# ZHSD-BOOT-STORAGE.net
KiCad netlist of a schematic drawn in Altium Designer
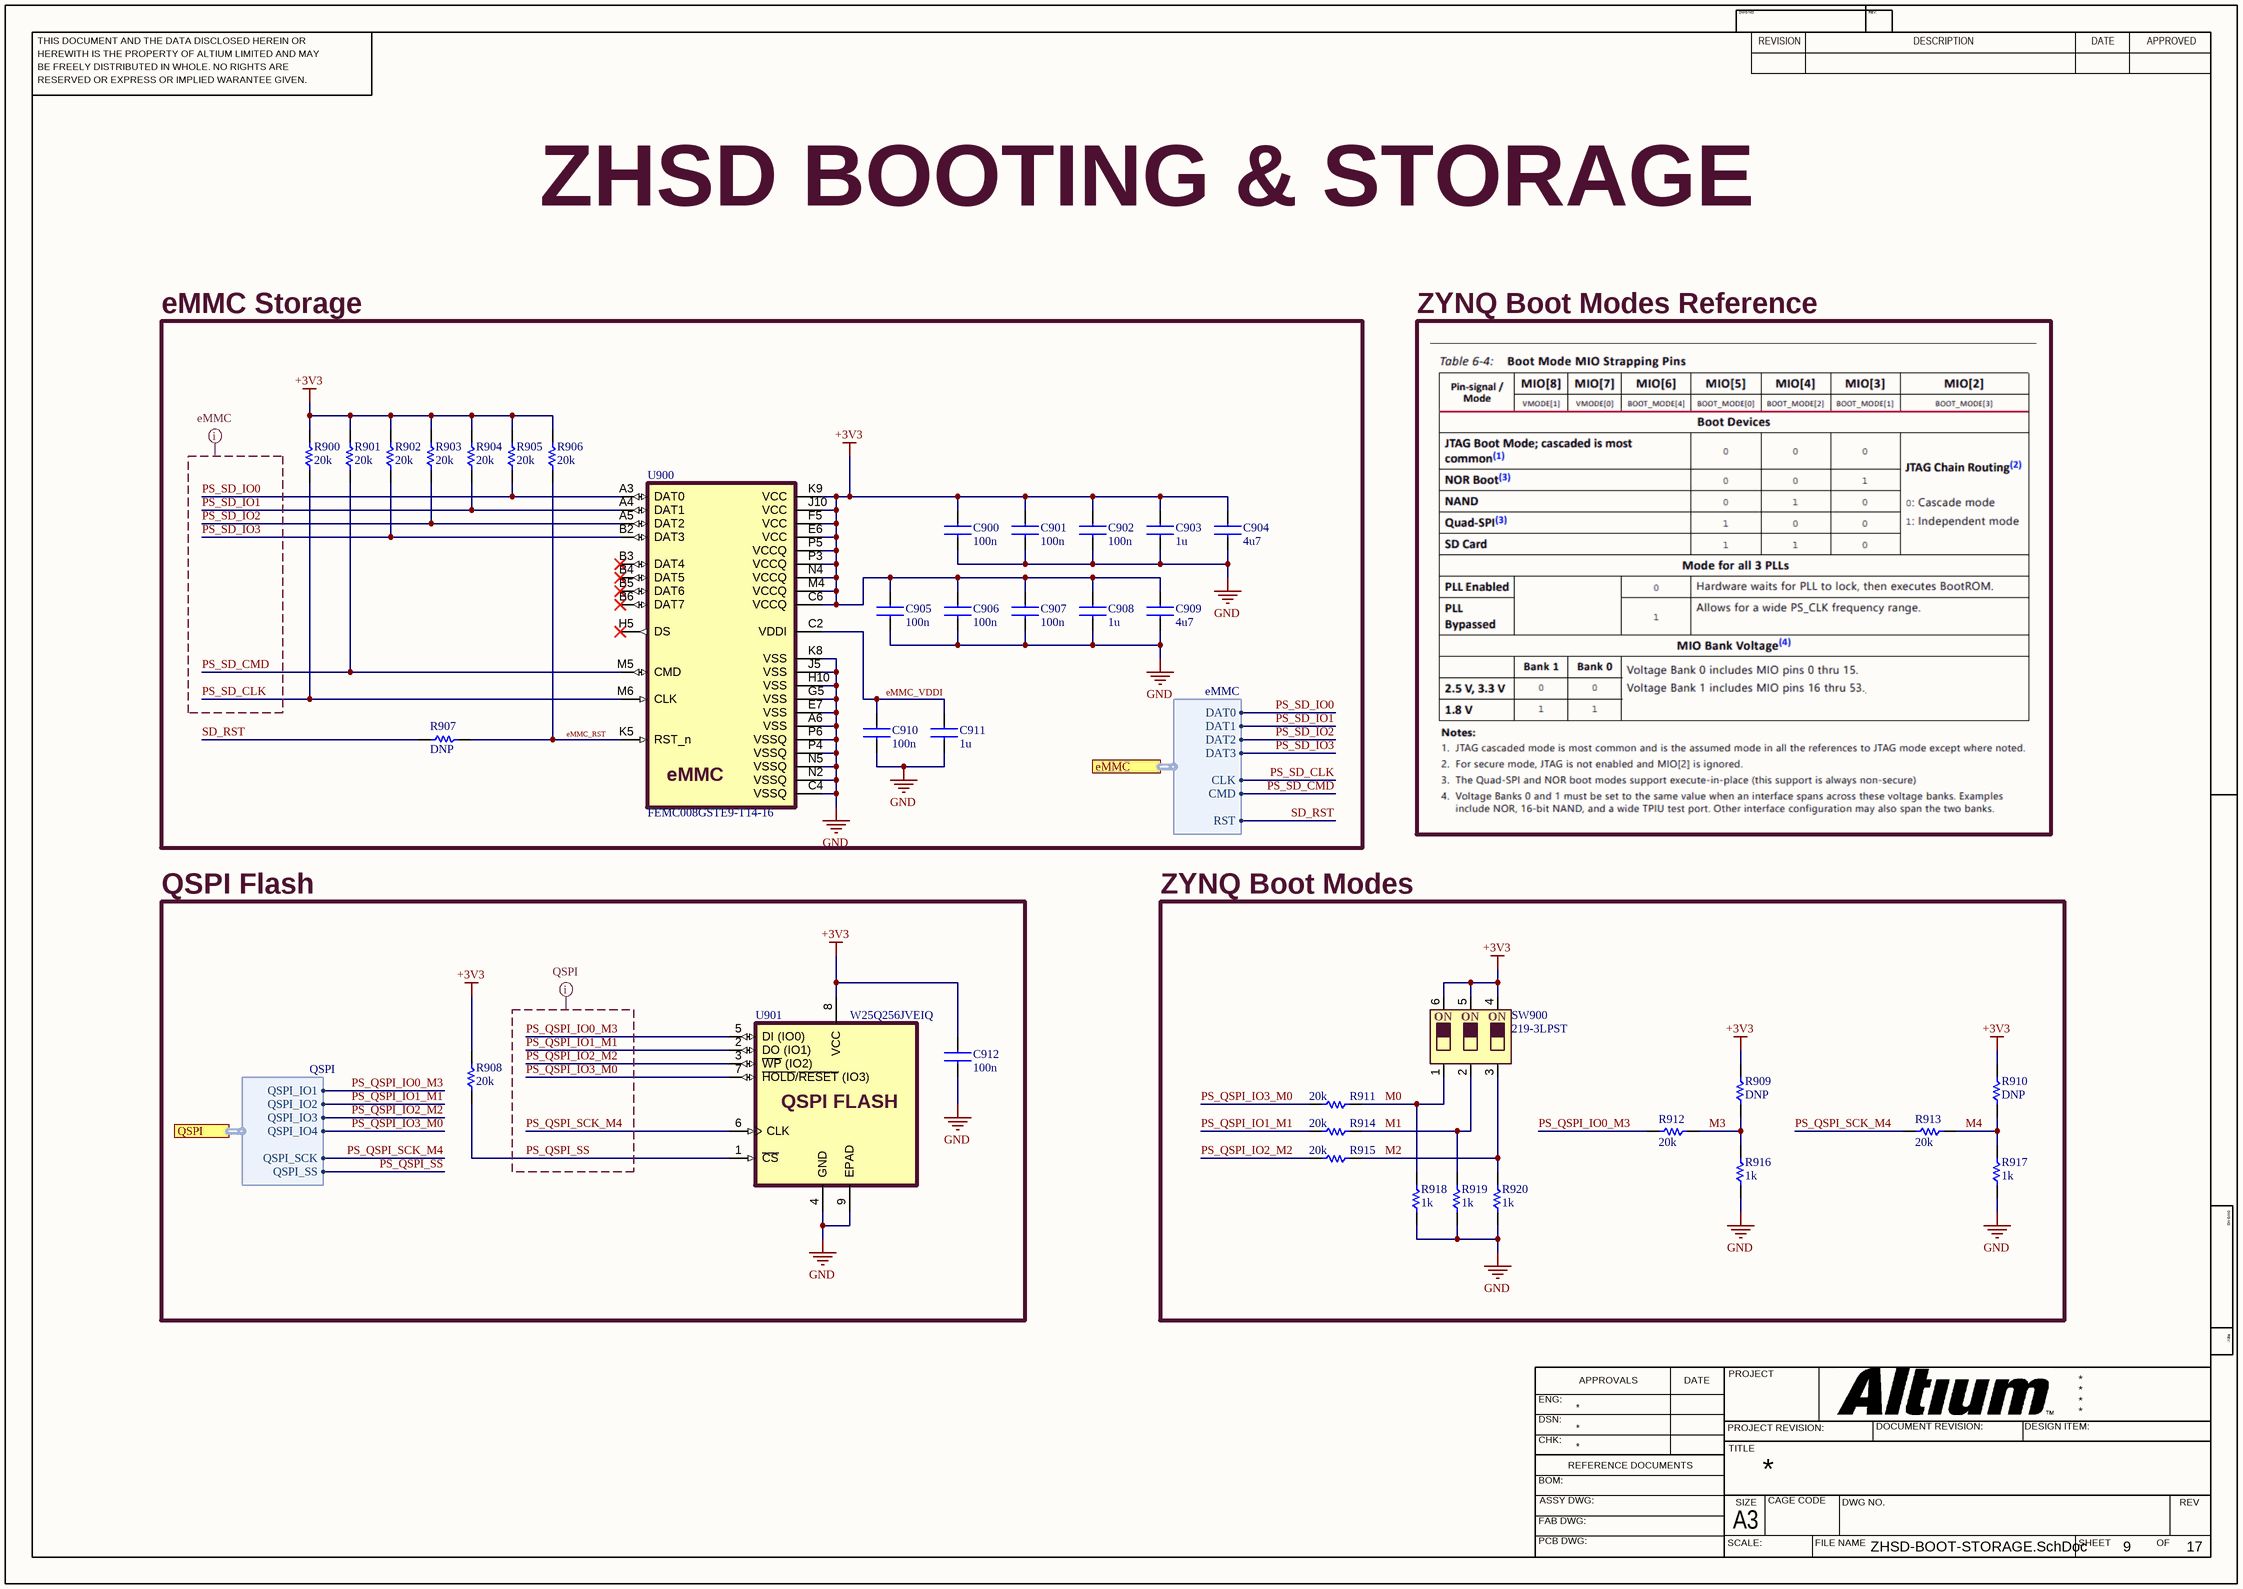
[diagram p0: ZHSD-BOOT-STORAGE.SchDoc]

(export (version "E")
  (design (tool "Eeschema 10.0.6"))
  (components
    (comp (ref "C900")
      (value "100n")
      (footprint "0603CAPC1608X09N")
      (description "CAP CER 0.1UF 16V X7R 0402 (1005) ±10%")
      (fields (field (name "MANUFACTURER") "Murata Electronics") (field (name "MPN") "GRM155R71C104KA88J"))
      (libsource (lib "UK_Library") (part "GRM155R71C104KA88J"))
    )
    (comp (ref "C901")
      (value "100n")
      (footprint "0603CAPC1608X09N")
      (description "CAP CER 0.1UF 16V X7R 0402 (1005) ±10%")
      (fields (field (name "MANUFACTURER") "Murata Electronics") (field (name "MPN") "GRM155R71C104KA88J"))
      (libsource (lib "UK_Library") (part "GRM155R71C104KA88J"))
    )
    (comp (ref "C902")
      (value "100n")
      (footprint "0603CAPC1608X09N")
      (description "CAP CER 0.1UF 16V X7R 0402 (1005) ±10%")
      (fields (field (name "MANUFACTURER") "Murata Electronics") (field (name "MPN") "GRM155R71C104KA88J"))
      (libsource (lib "UK_Library") (part "GRM155R71C104KA88J"))
    )
    (comp (ref "C903")
      (value "1u")
      (footprint "0603CAPC1608X09N")
      (description "CAP CER 1UF 25V X5R 0603 (1608) ±10%")
      (fields
        (field (name "MANUFACTURER") "Murata Power Solutions Inc.")
        (field (name "MPN") "GRM188R61E105KA12D")
      )
      (libsource (lib "UK_Library") (part "GRM188R61E105KA12D"))
    )
    (comp (ref "C904")
      (value "4u7")
      (footprint "0603CAPC1608X09N")
      (description "CAP CER 4.7UF 10V X5R 0603 (1608) ±10%")
      (fields
        (field (name "MANUFACTURER") "Samsung Electro-Mechanics")
        (field (name "MPN") "CL10A475KP8NNNC")
      )
      (libsource (lib "UK_Library") (part "CL10A475KP8NNNC"))
    )
    (comp (ref "C905")
      (value "100n")
      (footprint "0603CAPC1608X09N")
      (description "CAP CER 0.1UF 16V X7R 0402 (1005) ±10%")
      (fields (field (name "MANUFACTURER") "Murata Electronics") (field (name "MPN") "GRM155R71C104KA88J"))
      (libsource (lib "UK_Library") (part "GRM155R71C104KA88J"))
    )
    (comp (ref "C906")
      (value "100n")
      (footprint "0603CAPC1608X09N")
      (description "CAP CER 0.1UF 16V X7R 0402 (1005) ±10%")
      (fields (field (name "MANUFACTURER") "Murata Electronics") (field (name "MPN") "GRM155R71C104KA88J"))
      (libsource (lib "UK_Library") (part "GRM155R71C104KA88J"))
    )
    (comp (ref "C907")
      (value "100n")
      (footprint "0603CAPC1608X09N")
      (description "CAP CER 0.1UF 16V X7R 0402 (1005) ±10%")
      (fields (field (name "MANUFACTURER") "Murata Electronics") (field (name "MPN") "GRM155R71C104KA88J"))
      (libsource (lib "UK_Library") (part "GRM155R71C104KA88J"))
    )
    (comp (ref "C908")
      (value "1u")
      (footprint "0603CAPC1608X09N")
      (description "CAP CER 1UF 25V X5R 0603 (1608) ±10%")
      (fields
        (field (name "MANUFACTURER") "Murata Power Solutions Inc.")
        (field (name "MPN") "GRM188R61E105KA12D")
      )
      (libsource (lib "UK_Library") (part "GRM188R61E105KA12D"))
    )
    (comp (ref "C909")
      (value "4u7")
      (footprint "0603CAPC1608X09N")
      (description "CAP CER 4.7UF 10V X5R 0603 (1608) ±10%")
      (fields
        (field (name "MANUFACTURER") "Samsung Electro-Mechanics")
        (field (name "MPN") "CL10A475KP8NNNC")
      )
      (libsource (lib "UK_Library") (part "CL10A475KP8NNNC"))
    )
    (comp (ref "C910")
      (value "100n")
      (footprint "0603CAPC1608X09N")
      (description "CAP CER 0.1UF 16V X7R 0402 (1005) ±10%")
      (fields (field (name "MANUFACTURER") "Murata Electronics") (field (name "MPN") "GRM155R71C104KA88J"))
      (libsource (lib "UK_Library") (part "GRM155R71C104KA88J"))
    )
    (comp (ref "C911")
      (value "1u")
      (footprint "0603CAPC1608X09N")
      (description "CAP CER 1UF 25V X5R 0603 (1608) ±10%")
      (fields
        (field (name "MANUFACTURER") "Murata Power Solutions Inc.")
        (field (name "MPN") "GRM188R61E105KA12D")
      )
      (libsource (lib "UK_Library") (part "GRM188R61E105KA12D"))
    )
    (comp (ref "C912")
      (value "100n")
      (footprint "0603CAPC1608X09N")
      (description "CAP CER 0.1UF 16V X7R 0402 (1005) ±10%")
      (fields (field (name "MANUFACTURER") "Murata Electronics") (field (name "MPN") "GRM155R71C104KA88J"))
      (libsource (lib "UK_Library") (part "GRM155R71C104KA88J"))
    )
    (comp (ref "R900")
      (value "20k")
      (footprint "0402RESC1005X04N")
      (description "RES 20K OHM 1% 1/16W 0402 (1005)")
      (fields (field (name "MANUFACTURER") "YAGEO") (field (name "MPN") "RC0402FR-0720KL"))
      (libsource (lib "UK_Library") (part "RC0402FR-0720KL"))
    )
    (comp (ref "R901")
      (value "20k")
      (footprint "0402RESC1005X04N")
      (description "RES 20K OHM 1% 1/16W 0402 (1005)")
      (fields (field (name "MANUFACTURER") "YAGEO") (field (name "MPN") "RC0402FR-0720KL"))
      (libsource (lib "UK_Library") (part "RC0402FR-0720KL"))
    )
    (comp (ref "R902")
      (value "20k")
      (footprint "0402RESC1005X04N")
      (description "RES 20K OHM 1% 1/16W 0402 (1005)")
      (fields (field (name "MANUFACTURER") "YAGEO") (field (name "MPN") "RC0402FR-0720KL"))
      (libsource (lib "UK_Library") (part "RC0402FR-0720KL"))
    )
    (comp (ref "R903")
      (value "20k")
      (footprint "0402RESC1005X04N")
      (description "RES 20K OHM 1% 1/16W 0402 (1005)")
      (fields (field (name "MANUFACTURER") "YAGEO") (field (name "MPN") "RC0402FR-0720KL"))
      (libsource (lib "UK_Library") (part "RC0402FR-0720KL"))
    )
    (comp (ref "R904")
      (value "20k")
      (footprint "0402RESC1005X04N")
      (description "RES 20K OHM 1% 1/16W 0402 (1005)")
      (fields (field (name "MANUFACTURER") "YAGEO") (field (name "MPN") "RC0402FR-0720KL"))
      (libsource (lib "UK_Library") (part "RC0402FR-0720KL"))
    )
    (comp (ref "R905")
      (value "20k")
      (footprint "0402RESC1005X04N")
      (description "RES 20K OHM 1% 1/16W 0402 (1005)")
      (fields (field (name "MANUFACTURER") "YAGEO") (field (name "MPN") "RC0402FR-0720KL"))
      (libsource (lib "UK_Library") (part "RC0402FR-0720KL"))
    )
    (comp (ref "R906")
      (value "20k")
      (footprint "0402RESC1005X04N")
      (description "RES 20K OHM 1% 1/16W 0402 (1005)")
      (fields (field (name "MANUFACTURER") "YAGEO") (field (name "MPN") "RC0402FR-0720KL"))
      (libsource (lib "UK_Library") (part "RC0402FR-0720KL"))
    )
    (comp (ref "R907")
      (value "DNP")
      (footprint "0402RESC1005X04N")
      (description "DO NOT POPULATE RESISTOR")
      (fields (field (name "MANUFACTURER") "***"))
      (libsource (lib "UK_Library") (part "DNP_RES"))
    )
    (comp (ref "R908")
      (value "20k")
      (footprint "0402RESC1005X04N")
      (description "RES 20K OHM 1% 1/16W 0402 (1005)")
      (fields (field (name "MANUFACTURER") "YAGEO") (field (name "MPN") "RC0402FR-0720KL"))
      (libsource (lib "UK_Library") (part "RC0402FR-0720KL"))
    )
    (comp (ref "R909")
      (value "DNP")
      (footprint "0402RESC1005X04N")
      (description "DO NOT POPULATE RESISTOR")
      (fields (field (name "MANUFACTURER") "***"))
      (libsource (lib "UK_Library") (part "DNP_RES"))
    )
    (comp (ref "R910")
      (value "DNP")
      (footprint "0402RESC1005X04N")
      (description "DO NOT POPULATE RESISTOR")
      (fields (field (name "MANUFACTURER") "***"))
      (libsource (lib "UK_Library") (part "DNP_RES"))
    )
    (comp (ref "R911")
      (value "20k")
      (footprint "0402RESC1005X04N")
      (description "RES 20K OHM 1% 1/16W 0402 (1005)")
      (fields (field (name "MANUFACTURER") "YAGEO") (field (name "MPN") "RC0402FR-0720KL"))
      (libsource (lib "UK_Library") (part "RC0402FR-0720KL"))
    )
    (comp (ref "R912")
      (value "20k")
      (footprint "0402RESC1005X04N")
      (description "RES 20K OHM 1% 1/16W 0402 (1005)")
      (fields (field (name "MANUFACTURER") "YAGEO") (field (name "MPN") "RC0402FR-0720KL"))
      (libsource (lib "UK_Library") (part "RC0402FR-0720KL"))
    )
    (comp (ref "R913")
      (value "20k")
      (footprint "0402RESC1005X04N")
      (description "RES 20K OHM 1% 1/16W 0402 (1005)")
      (fields (field (name "MANUFACTURER") "YAGEO") (field (name "MPN") "RC0402FR-0720KL"))
      (libsource (lib "UK_Library") (part "RC0402FR-0720KL"))
    )
    (comp (ref "R914")
      (value "20k")
      (footprint "0402RESC1005X04N")
      (description "RES 20K OHM 1% 1/16W 0402 (1005)")
      (fields (field (name "MANUFACTURER") "YAGEO") (field (name "MPN") "RC0402FR-0720KL"))
      (libsource (lib "UK_Library") (part "RC0402FR-0720KL"))
    )
    (comp (ref "R915")
      (value "20k")
      (footprint "0402RESC1005X04N")
      (description "RES 20K OHM 1% 1/16W 0402 (1005)")
      (fields (field (name "MANUFACTURER") "YAGEO") (field (name "MPN") "RC0402FR-0720KL"))
      (libsource (lib "UK_Library") (part "RC0402FR-0720KL"))
    )
    (comp (ref "R916")
      (value "1k")
      (footprint "0402RESC1005X04N")
      (description "RES 1K OHM 5% 1/16W 0402 (1005)")
      (fields (field (name "MANUFACTURER") "YAGEO") (field (name "MPN") "RC0402JR-071KL"))
      (libsource (lib "UK_Library") (part "RC0402JR-071KL"))
    )
    (comp (ref "R917")
      (value "1k")
      (footprint "0402RESC1005X04N")
      (description "RES 1K OHM 5% 1/16W 0402 (1005)")
      (fields (field (name "MANUFACTURER") "YAGEO") (field (name "MPN") "RC0402JR-071KL"))
      (libsource (lib "UK_Library") (part "RC0402JR-071KL"))
    )
    (comp (ref "R918")
      (value "1k")
      (footprint "0402RESC1005X04N")
      (description "RES 1K OHM 5% 1/16W 0402 (1005)")
      (fields (field (name "MANUFACTURER") "YAGEO") (field (name "MPN") "RC0402JR-071KL"))
      (libsource (lib "UK_Library") (part "RC0402JR-071KL"))
    )
    (comp (ref "R919")
      (value "1k")
      (footprint "0402RESC1005X04N")
      (description "RES 1K OHM 5% 1/16W 0402 (1005)")
      (fields (field (name "MANUFACTURER") "YAGEO") (field (name "MPN") "RC0402JR-071KL"))
      (libsource (lib "UK_Library") (part "RC0402JR-071KL"))
    )
    (comp (ref "R920")
      (value "1k")
      (footprint "0402RESC1005X04N")
      (description "RES 1K OHM 5% 1/16W 0402 (1005)")
      (fields (field (name "MANUFACTURER") "YAGEO") (field (name "MPN") "RC0402JR-071KL"))
      (libsource (lib "UK_Library") (part "RC0402JR-071KL"))
    )
    (comp (ref "SW900")
      (value "219-3LPST")
      (footprint "219-3LPST")
      (description "Dip Switch SPST 3 Position Surface Mount Slide (Standard) Actuator 100mA 20VDC")
      (fields (field (name "MANUFACTURER") "CTS Electrocomponents"))
      (libsource (lib "UK_Library") (part "219-3LPST"))
    )
    (comp (ref "U900")
      (value "FEMC008GSTE9-T14-16")
      (footprint "BGA153C50P14X14_1150X1300X100")
      (description "FLASH - NAND (MLC) Memory IC 64Gbit eMMC_5.1 200 MHz 153-FBGA (11.5x13)")
      (fields (field (name "MANUFACTURER") "Flexxon Pte Ltd"))
      (libsource (lib "UK_Library") (part "FEMC008GSTE9-T14-16"))
    )
    (comp (ref "U901")
      (value "W25Q256JVEIQ")
      (footprint "WSON8X6-SON127P800X80_HS-9N")
      (description "FLASH - NOR Memory IC 256Mbit SPI - Quad I/O 133 MHz 8-WSON (8x6)")
      (fields (field (name "MANUFACTURER") "Winbond Electronics"))
      (libsource (lib "UK_Library") (part "W25Q256JVEIQ"))
    )
  )
  (nets
    (net (code "3") (name "+3V3") (class "Default")
      (node (ref "C900") (pin "2") (pinfunction "2_2") (pintype "passive"))
      (node (ref "C901") (pin "2") (pinfunction "2_2") (pintype "passive"))
      (node (ref "C902") (pin "2") (pinfunction "2_2") (pintype "passive"))
      (node (ref "C903") (pin "2") (pinfunction "2_2") (pintype "passive"))
      (node (ref "C904") (pin "2") (pinfunction "2_2") (pintype "passive"))
      (node (ref "C905") (pin "2") (pinfunction "2_2") (pintype "passive"))
      (node (ref "C906") (pin "2") (pinfunction "2_2") (pintype "passive"))
      (node (ref "C907") (pin "2") (pinfunction "2_2") (pintype "passive"))
      (node (ref "C908") (pin "2") (pinfunction "2_2") (pintype "passive"))
      (node (ref "C909") (pin "2") (pinfunction "2_2") (pintype "passive"))
      (node (ref "C912") (pin "2") (pinfunction "2_2") (pintype "passive"))
      (node (ref "R900") (pin "2") (pinfunction "2_2") (pintype "passive"))
      (node (ref "R901") (pin "2") (pinfunction "2_2") (pintype "passive"))
      (node (ref "R902") (pin "2") (pinfunction "2_2") (pintype "passive"))
      (node (ref "R903") (pin "2") (pinfunction "2_2") (pintype "passive"))
      (node (ref "R904") (pin "2") (pinfunction "2_2") (pintype "passive"))
      (node (ref "R905") (pin "2") (pinfunction "2_2") (pintype "passive"))
      (node (ref "R906") (pin "2") (pinfunction "2_2") (pintype "passive"))
      (node (ref "R908") (pin "2") (pinfunction "2_2") (pintype "passive"))
      (node (ref "R909") (pin "2") (pinfunction "2_2") (pintype "passive"))
      (node (ref "R910") (pin "2") (pinfunction "2_2") (pintype "passive"))
      (node (ref "SW900") (pin "4") (pinfunction "4_4") (pintype "passive"))
      (node (ref "SW900") (pin "5") (pinfunction "5_5") (pintype "passive"))
      (node (ref "SW900") (pin "6") (pinfunction "6_6") (pintype "passive"))
      (node (ref "U900") (pin "C6") (pinfunction "VCCQ_C6") (pintype "power_in"))
      (node (ref "U900") (pin "E6") (pinfunction "VCC_E6") (pintype "power_in"))
      (node (ref "U900") (pin "F5") (pinfunction "VCC_F5") (pintype "power_in"))
      (node (ref "U900") (pin "J10") (pinfunction "VCC_J10") (pintype "power_in"))
      (node (ref "U900") (pin "K9") (pinfunction "VCC_K9") (pintype "power_in"))
      (node (ref "U900") (pin "M4") (pinfunction "VCCQ_M4") (pintype "power_in"))
      (node (ref "U900") (pin "N4") (pinfunction "VCCQ_N4") (pintype "power_in"))
      (node (ref "U900") (pin "P3") (pinfunction "VCCQ_P3") (pintype "power_in"))
      (node (ref "U900") (pin "P5") (pinfunction "VCCQ_P5") (pintype "power_in"))
      (node (ref "U901") (pin "8") (pinfunction "VCC_8") (pintype "power_in"))
    )
    (net (code "4") (name "/M0") (class "Default")
      (node (ref "R911") (pin "1") (pinfunction "1_1") (pintype "passive"))
      (node (ref "R918") (pin "2") (pinfunction "2_2") (pintype "passive"))
      (node (ref "SW900") (pin "1") (pinfunction "1_1") (pintype "passive"))
    )
    (net (code "5") (name "/M1") (class "Default")
      (node (ref "R914") (pin "1") (pinfunction "1_1") (pintype "passive"))
      (node (ref "R919") (pin "2") (pinfunction "2_2") (pintype "passive"))
      (node (ref "SW900") (pin "2") (pinfunction "2_2") (pintype "passive"))
    )
    (net (code "6") (name "/M2") (class "Default")
      (node (ref "R915") (pin "1") (pinfunction "1_1") (pintype "passive"))
      (node (ref "R920") (pin "2") (pinfunction "2_2") (pintype "passive"))
      (node (ref "SW900") (pin "3") (pinfunction "3_3") (pintype "passive"))
    )
    (net (code "7") (name "/M3") (class "Default")
      (node (ref "R909") (pin "1") (pinfunction "1_1") (pintype "passive"))
      (node (ref "R912") (pin "1") (pinfunction "1_1") (pintype "passive"))
      (node (ref "R916") (pin "2") (pinfunction "2_2") (pintype "passive"))
    )
    (net (code "8") (name "/M4") (class "Default")
      (node (ref "R910") (pin "1") (pinfunction "1_1") (pintype "passive"))
      (node (ref "R913") (pin "1") (pinfunction "1_1") (pintype "passive"))
      (node (ref "R917") (pin "2") (pinfunction "2_2") (pintype "passive"))
    )
    (net (code "9") (name "/PS_QSPI_IO0_M3") (class "Default")
      (node (ref "R912") (pin "2") (pinfunction "2_2") (pintype "passive"))
      (node (ref "U901") (pin "5") (pinfunction "DI_(IO0)_5") (pintype "bidirectional"))
    )
    (net (code "10") (name "/PS_QSPI_IO1_M1") (class "Default")
      (node (ref "R914") (pin "2") (pinfunction "2_2") (pintype "passive"))
      (node (ref "U901") (pin "2") (pinfunction "DO_(IO1)_2") (pintype "bidirectional"))
    )
    (net (code "11") (name "/PS_QSPI_IO2_M2") (class "Default")
      (node (ref "R915") (pin "2") (pinfunction "2_2") (pintype "passive"))
      (node (ref "U901") (pin "3") (pinfunction "~{WP}_(IO2)_3") (pintype "bidirectional"))
    )
    (net (code "12") (name "/PS_QSPI_IO3_M0") (class "Default")
      (node (ref "R911") (pin "2") (pinfunction "2_2") (pintype "passive"))
      (node (ref "U901") (pin "7") (pinfunction "~{HOLD}/~{RESET}_(IO3)_7") (pintype "bidirectional"))
    )
    (net (code "13") (name "/PS_QSPI_SCK_M4") (class "Default")
      (node (ref "R913") (pin "2") (pinfunction "2_2") (pintype "passive"))
      (node (ref "U901") (pin "6") (pinfunction "CLK_6") (pintype "input"))
    )
    (net (code "14") (name "/PS_QSPI_SS") (class "Default")
      (node (ref "R908") (pin "1") (pinfunction "1_1") (pintype "passive"))
      (node (ref "U901") (pin "1") (pinfunction "~{CS}_1") (pintype "input"))
    )
    (net (code "15") (name "/PS_SD_CLK") (class "Default")
      (node (ref "R900") (pin "1") (pinfunction "1_1") (pintype "passive"))
      (node (ref "U900") (pin "M6") (pinfunction "CLK_M6") (pintype "input"))
    )
    (net (code "16") (name "/PS_SD_CMD") (class "Default")
      (node (ref "R901") (pin "1") (pinfunction "1_1") (pintype "passive"))
      (node (ref "U900") (pin "M5") (pinfunction "CMD_M5") (pintype "bidirectional"))
    )
    (net (code "17") (name "/PS_SD_IO0") (class "Default")
      (node (ref "R905") (pin "1") (pinfunction "1_1") (pintype "passive"))
      (node (ref "U900") (pin "A3") (pinfunction "DAT0_A3") (pintype "bidirectional"))
    )
    (net (code "18") (name "/PS_SD_IO1") (class "Default")
      (node (ref "R904") (pin "1") (pinfunction "1_1") (pintype "passive"))
      (node (ref "U900") (pin "A4") (pinfunction "DAT1_A4") (pintype "bidirectional"))
    )
    (net (code "19") (name "/PS_SD_IO2") (class "Default")
      (node (ref "R903") (pin "1") (pinfunction "1_1") (pintype "passive"))
      (node (ref "U900") (pin "A5") (pinfunction "DAT2_A5") (pintype "bidirectional"))
    )
    (net (code "20") (name "/PS_SD_IO3") (class "Default")
      (node (ref "R902") (pin "1") (pinfunction "1_1") (pintype "passive"))
      (node (ref "U900") (pin "B2") (pinfunction "DAT3_B2") (pintype "bidirectional"))
    )
    (net (code "21") (name "/SD_RST") (class "Default")
      (node (ref "R907") (pin "1") (pinfunction "1_1") (pintype "passive"))
    )
    (net (code "22") (name "/eMMC_RST") (class "Default")
      (node (ref "R906") (pin "1") (pinfunction "1_1") (pintype "passive"))
      (node (ref "R907") (pin "2") (pinfunction "2_2") (pintype "passive"))
      (node (ref "U900") (pin "K5") (pinfunction "RST_n_K5") (pintype "input"))
    )
    (net (code "23") (name "/eMMC_VDDI") (class "Default")
      (node (ref "C910") (pin "2") (pinfunction "2_2") (pintype "passive"))
      (node (ref "C911") (pin "2") (pinfunction "2_2") (pintype "passive"))
      (node (ref "U900") (pin "C2") (pinfunction "VDDI_C2") (pintype "power_in"))
    )
    (net (code "26") (name "GND") (class "Default")
      (node (ref "C900") (pin "1") (pinfunction "1_1") (pintype "passive"))
      (node (ref "C901") (pin "1") (pinfunction "1_1") (pintype "passive"))
      (node (ref "C902") (pin "1") (pinfunction "1_1") (pintype "passive"))
      (node (ref "C903") (pin "1") (pinfunction "1_1") (pintype "passive"))
      (node (ref "C904") (pin "1") (pinfunction "1_1") (pintype "passive"))
      (node (ref "C905") (pin "1") (pinfunction "1_1") (pintype "passive"))
      (node (ref "C906") (pin "1") (pinfunction "1_1") (pintype "passive"))
      (node (ref "C907") (pin "1") (pinfunction "1_1") (pintype "passive"))
      (node (ref "C908") (pin "1") (pinfunction "1_1") (pintype "passive"))
      (node (ref "C909") (pin "1") (pinfunction "1_1") (pintype "passive"))
      (node (ref "C910") (pin "1") (pinfunction "1_1") (pintype "passive"))
      (node (ref "C911") (pin "1") (pinfunction "1_1") (pintype "passive"))
      (node (ref "C912") (pin "1") (pinfunction "1_1") (pintype "passive"))
      (node (ref "R916") (pin "1") (pinfunction "1_1") (pintype "passive"))
      (node (ref "R917") (pin "1") (pinfunction "1_1") (pintype "passive"))
      (node (ref "R918") (pin "1") (pinfunction "1_1") (pintype "passive"))
      (node (ref "R919") (pin "1") (pinfunction "1_1") (pintype "passive"))
      (node (ref "R920") (pin "1") (pinfunction "1_1") (pintype "passive"))
      (node (ref "U900") (pin "A6") (pinfunction "VSS_A6") (pintype "power_in"))
      (node (ref "U900") (pin "C4") (pinfunction "VSSQ_C4") (pintype "power_in"))
      (node (ref "U900") (pin "E7") (pinfunction "VSS_E7") (pintype "power_in"))
      (node (ref "U900") (pin "G5") (pinfunction "VSS_G5") (pintype "power_in"))
      (node (ref "U900") (pin "H10") (pinfunction "VSS_H10") (pintype "power_in"))
      (node (ref "U900") (pin "J5") (pinfunction "VSS_J5") (pintype "power_in"))
      (node (ref "U900") (pin "K8") (pinfunction "VSS_K8") (pintype "power_in"))
      (node (ref "U900") (pin "N2") (pinfunction "VSSQ_N2") (pintype "power_in"))
      (node (ref "U900") (pin "N5") (pinfunction "VSSQ_N5") (pintype "power_in"))
      (node (ref "U900") (pin "P4") (pinfunction "VSSQ_P4") (pintype "power_in"))
      (node (ref "U900") (pin "P6") (pinfunction "VSSQ_P6") (pintype "power_in"))
      (node (ref "U901") (pin "4") (pinfunction "GND_4") (pintype "power_in"))
      (node (ref "U901") (pin "9") (pinfunction "EPAD_9") (pintype "power_in"))
    )
    (net (code "27") (name "unconnected-(U900-DAT4-PadB3)") (class "Default")
      (node (ref "U900") (pin "B3") (pinfunction "DAT4_B3") (pintype "bidirectional+no_connect"))
    )
    (net (code "28") (name "unconnected-(U900-DAT5-PadB4)") (class "Default")
      (node (ref "U900") (pin "B4") (pinfunction "DAT5_B4") (pintype "bidirectional+no_connect"))
    )
    (net (code "29") (name "unconnected-(U900-DAT6-PadB5)") (class "Default")
      (node (ref "U900") (pin "B5") (pinfunction "DAT6_B5") (pintype "bidirectional+no_connect"))
    )
    (net (code "30") (name "unconnected-(U900-DAT7-PadB6)") (class "Default")
      (node (ref "U900") (pin "B6") (pinfunction "DAT7_B6") (pintype "bidirectional+no_connect"))
    )
    (net (code "31") (name "unconnected-(U900-DS-PadH5)") (class "Default")
      (node (ref "U900") (pin "H5") (pinfunction "DS_H5") (pintype "output+no_connect"))
    )
  )
)
